# programmer-board.net
KiCad netlist of a schematic drawn in EAGLE
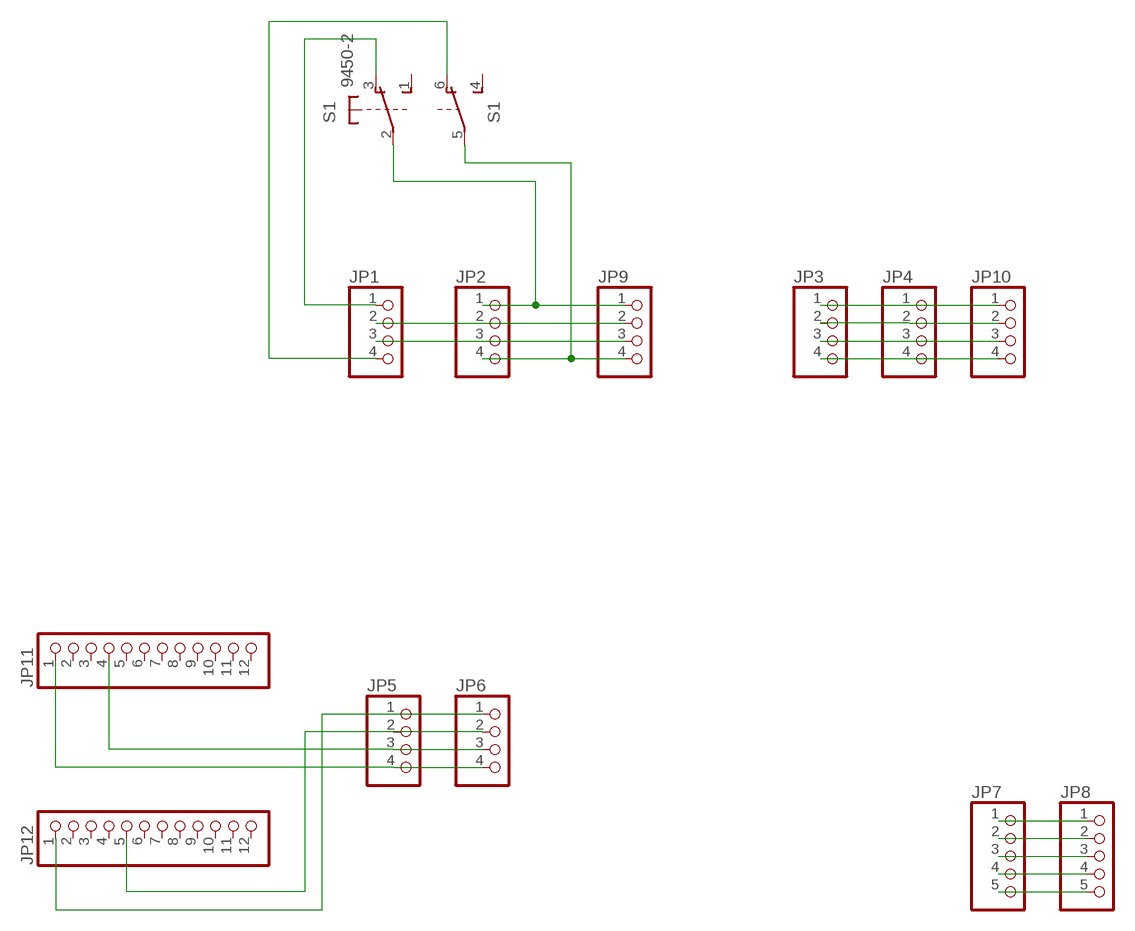
[diagram p0: schematic, sheet 1]

(export (version "E")
  (design (tool "Eeschema 10.0.6"))
  (components
    (comp (ref "JP1")
      (value "PINHD-1X4")
      (footprint "eagle-import:1X04")
      (libsource (lib "eagle-import") (part "PINHD-1X4"))
    )
    (comp (ref "JP2")
      (value "PINHD-1X4")
      (footprint "eagle-import:1X04")
      (libsource (lib "eagle-import") (part "PINHD-1X4"))
    )
    (comp (ref "JP3")
      (value "PINHD-1X4")
      (footprint "eagle-import:1X04")
      (libsource (lib "eagle-import") (part "PINHD-1X4"))
    )
    (comp (ref "JP4")
      (value "PINHD-1X4")
      (footprint "eagle-import:1X04")
      (libsource (lib "eagle-import") (part "PINHD-1X4"))
    )
    (comp (ref "JP5")
      (value "PINHD-1X4")
      (footprint "eagle-import:1X04")
      (libsource (lib "eagle-import") (part "PINHD-1X4"))
    )
    (comp (ref "JP6")
      (value "PINHD-1X4")
      (footprint "eagle-import:1X04")
      (libsource (lib "eagle-import") (part "PINHD-1X4"))
    )
    (comp (ref "JP7")
      (value "PINHD-1X5")
      (footprint "eagle-import:1X05")
      (libsource (lib "eagle-import") (part "PINHD-1X5"))
    )
    (comp (ref "JP8")
      (value "PINHD-1X5")
      (footprint "eagle-import:1X05")
      (libsource (lib "eagle-import") (part "PINHD-1X5"))
    )
    (comp (ref "JP9")
      (value "PINHD-1X4")
      (footprint "eagle-import:1X04")
      (libsource (lib "eagle-import") (part "PINHD-1X4"))
    )
    (comp (ref "JP10")
      (value "PINHD-1X4")
      (footprint "eagle-import:1X04")
      (libsource (lib "eagle-import") (part "PINHD-1X4"))
    )
    (comp (ref "JP11")
      (value "PINHD-1X12")
      (footprint "eagle-import:1X12")
      (libsource (lib "eagle-import") (part "PINHD-1X12"))
    )
    (comp (ref "JP12")
      (value "PINHD-1X12")
      (footprint "eagle-import:1X12")
      (libsource (lib "eagle-import") (part "PINHD-1X12"))
    )
    (comp (ref "S1")
      (value "9450-2")
      (footprint "eagle-import:9450-2")
      (libsource (lib "eagle-import") (part "9450-2"))
    )
  )
  (nets
    (net (code "1") (name "Net-(JP1-Pad2)") (class "Default")
      (node (ref "JP1") (pin "2") (pinfunction "2_2") (pintype "passive"))
      (node (ref "JP2") (pin "2") (pinfunction "2_2") (pintype "passive"))
      (node (ref "JP9") (pin "2") (pinfunction "2_2") (pintype "passive"))
    )
    (net (code "2") (name "Net-(JP1-Pad3)") (class "Default")
      (node (ref "JP1") (pin "3") (pinfunction "3_3") (pintype "passive"))
      (node (ref "JP2") (pin "3") (pinfunction "3_3") (pintype "passive"))
      (node (ref "JP9") (pin "3") (pinfunction "3_3") (pintype "passive"))
    )
    (net (code "3") (name "Net-(JP7-Pad1)") (class "Default")
      (node (ref "JP7") (pin "1") (pinfunction "1_1") (pintype "passive"))
      (node (ref "JP8") (pin "1") (pinfunction "1_1") (pintype "passive"))
    )
    (net (code "4") (name "Net-(JP7-Pad2)") (class "Default")
      (node (ref "JP7") (pin "2") (pinfunction "2_2") (pintype "passive"))
      (node (ref "JP8") (pin "2") (pinfunction "2_2") (pintype "passive"))
    )
    (net (code "5") (name "Net-(JP7-Pad3)") (class "Default")
      (node (ref "JP7") (pin "3") (pinfunction "3_3") (pintype "passive"))
      (node (ref "JP8") (pin "3") (pinfunction "3_3") (pintype "passive"))
    )
    (net (code "6") (name "Net-(JP7-Pad4)") (class "Default")
      (node (ref "JP7") (pin "4") (pinfunction "4_4") (pintype "passive"))
      (node (ref "JP8") (pin "4") (pinfunction "4_4") (pintype "passive"))
    )
    (net (code "7") (name "Net-(JP7-Pad5)") (class "Default")
      (node (ref "JP7") (pin "5") (pinfunction "5_5") (pintype "passive"))
      (node (ref "JP8") (pin "5") (pinfunction "5_5") (pintype "passive"))
    )
    (net (code "8") (name "Net-(JP10-Pad1)") (class "Default")
      (node (ref "JP10") (pin "1") (pinfunction "1_1") (pintype "passive"))
      (node (ref "JP3") (pin "1") (pinfunction "1_1") (pintype "passive"))
      (node (ref "JP4") (pin "1") (pinfunction "1_1") (pintype "passive"))
    )
    (net (code "9") (name "Net-(JP10-Pad2)") (class "Default")
      (node (ref "JP10") (pin "2") (pinfunction "2_2") (pintype "passive"))
      (node (ref "JP3") (pin "2") (pinfunction "2_2") (pintype "passive"))
      (node (ref "JP4") (pin "2") (pinfunction "2_2") (pintype "passive"))
    )
    (net (code "10") (name "Net-(JP10-Pad3)") (class "Default")
      (node (ref "JP10") (pin "3") (pinfunction "3_3") (pintype "passive"))
      (node (ref "JP3") (pin "3") (pinfunction "3_3") (pintype "passive"))
      (node (ref "JP4") (pin "3") (pinfunction "3_3") (pintype "passive"))
    )
    (net (code "11") (name "Net-(JP10-Pad4)") (class "Default")
      (node (ref "JP10") (pin "4") (pinfunction "4_4") (pintype "passive"))
      (node (ref "JP3") (pin "4") (pinfunction "4_4") (pintype "passive"))
      (node (ref "JP4") (pin "4") (pinfunction "4_4") (pintype "passive"))
    )
    (net (code "12") (name "Net-(JP11-Pad1)") (class "Default")
      (node (ref "JP11") (pin "1") (pinfunction "1_1") (pintype "passive"))
      (node (ref "JP5") (pin "4") (pinfunction "4_4") (pintype "passive"))
      (node (ref "JP6") (pin "4") (pinfunction "4_4") (pintype "passive"))
    )
    (net (code "13") (name "Net-(JP11-Pad4)") (class "Default")
      (node (ref "JP11") (pin "4") (pinfunction "4_4") (pintype "passive"))
      (node (ref "JP5") (pin "3") (pinfunction "3_3") (pintype "passive"))
      (node (ref "JP6") (pin "3") (pinfunction "3_3") (pintype "passive"))
    )
    (net (code "14") (name "Net-(JP12-Pad1)") (class "Default")
      (node (ref "JP12") (pin "1") (pinfunction "1_1") (pintype "passive"))
      (node (ref "JP5") (pin "1") (pinfunction "1_1") (pintype "passive"))
      (node (ref "JP6") (pin "1") (pinfunction "1_1") (pintype "passive"))
    )
    (net (code "15") (name "Net-(JP12-Pad5)") (class "Default")
      (node (ref "JP12") (pin "5") (pinfunction "5_5") (pintype "passive"))
      (node (ref "JP5") (pin "2") (pinfunction "2_2") (pintype "passive"))
      (node (ref "JP6") (pin "2") (pinfunction "2_2") (pintype "passive"))
    )
    (net (code "16") (name "Net-(S1A-O)") (class "Default")
      (node (ref "JP1") (pin "1") (pinfunction "1_1") (pintype "passive"))
      (node (ref "S1") (pin "3") (pinfunction "O_3") (pintype "passive"))
    )
    (net (code "17") (name "Net-(S1A-P)") (class "Default")
      (node (ref "JP2") (pin "1") (pinfunction "1_1") (pintype "passive"))
      (node (ref "JP9") (pin "1") (pinfunction "1_1") (pintype "passive"))
      (node (ref "S1") (pin "2") (pinfunction "P_2") (pintype "passive"))
    )
    (net (code "18") (name "Net-(S1B-O)") (class "Default")
      (node (ref "JP1") (pin "4") (pinfunction "4_4") (pintype "passive"))
      (node (ref "S1") (pin "6") (pinfunction "O_6") (pintype "passive"))
    )
    (net (code "19") (name "Net-(S1B-P)") (class "Default")
      (node (ref "JP2") (pin "4") (pinfunction "4_4") (pintype "passive"))
      (node (ref "JP9") (pin "4") (pinfunction "4_4") (pintype "passive"))
      (node (ref "S1") (pin "5") (pinfunction "P_5") (pintype "passive"))
    )
    (net (code "20") (name "unconnected-(JP11-Pad2)") (class "Default")
      (node (ref "JP11") (pin "2") (pinfunction "2_2") (pintype "passive"))
    )
    (net (code "21") (name "unconnected-(JP11-Pad3)") (class "Default")
      (node (ref "JP11") (pin "3") (pinfunction "3_3") (pintype "passive"))
    )
    (net (code "22") (name "unconnected-(JP11-Pad5)") (class "Default")
      (node (ref "JP11") (pin "5") (pinfunction "5_5") (pintype "passive"))
    )
    (net (code "23") (name "unconnected-(JP11-Pad6)") (class "Default")
      (node (ref "JP11") (pin "6") (pinfunction "6_6") (pintype "passive"))
    )
    (net (code "24") (name "unconnected-(JP11-Pad7)") (class "Default")
      (node (ref "JP11") (pin "7") (pinfunction "7_7") (pintype "passive"))
    )
    (net (code "25") (name "unconnected-(JP11-Pad8)") (class "Default")
      (node (ref "JP11") (pin "8") (pinfunction "8_8") (pintype "passive"))
    )
    (net (code "26") (name "unconnected-(JP11-Pad9)") (class "Default")
      (node (ref "JP11") (pin "9") (pinfunction "9_9") (pintype "passive"))
    )
    (net (code "27") (name "unconnected-(JP11-Pad10)") (class "Default")
      (node (ref "JP11") (pin "10") (pinfunction "10_10") (pintype "passive"))
    )
    (net (code "28") (name "unconnected-(JP11-Pad11)") (class "Default")
      (node (ref "JP11") (pin "11") (pinfunction "11_11") (pintype "passive"))
    )
    (net (code "29") (name "unconnected-(JP11-Pad12)") (class "Default")
      (node (ref "JP11") (pin "12") (pinfunction "12_12") (pintype "passive"))
    )
    (net (code "30") (name "unconnected-(JP12-Pad2)") (class "Default")
      (node (ref "JP12") (pin "2") (pinfunction "2_2") (pintype "passive"))
    )
    (net (code "31") (name "unconnected-(JP12-Pad3)") (class "Default")
      (node (ref "JP12") (pin "3") (pinfunction "3_3") (pintype "passive"))
    )
    (net (code "32") (name "unconnected-(JP12-Pad4)") (class "Default")
      (node (ref "JP12") (pin "4") (pinfunction "4_4") (pintype "passive"))
    )
    (net (code "33") (name "unconnected-(JP12-Pad6)") (class "Default")
      (node (ref "JP12") (pin "6") (pinfunction "6_6") (pintype "passive"))
    )
    (net (code "34") (name "unconnected-(JP12-Pad7)") (class "Default")
      (node (ref "JP12") (pin "7") (pinfunction "7_7") (pintype "passive"))
    )
    (net (code "35") (name "unconnected-(JP12-Pad8)") (class "Default")
      (node (ref "JP12") (pin "8") (pinfunction "8_8") (pintype "passive"))
    )
    (net (code "36") (name "unconnected-(JP12-Pad9)") (class "Default")
      (node (ref "JP12") (pin "9") (pinfunction "9_9") (pintype "passive"))
    )
    (net (code "37") (name "unconnected-(JP12-Pad10)") (class "Default")
      (node (ref "JP12") (pin "10") (pinfunction "10_10") (pintype "passive"))
    )
    (net (code "38") (name "unconnected-(JP12-Pad11)") (class "Default")
      (node (ref "JP12") (pin "11") (pinfunction "11_11") (pintype "passive"))
    )
    (net (code "39") (name "unconnected-(JP12-Pad12)") (class "Default")
      (node (ref "JP12") (pin "12") (pinfunction "12_12") (pintype "passive"))
    )
    (net (code "40") (name "unconnected-(S1A-S-Pad1)") (class "Default")
      (node (ref "S1") (pin "1") (pinfunction "S_1") (pintype "passive"))
    )
    (net (code "41") (name "unconnected-(S1B-S-Pad4)") (class "Default")
      (node (ref "S1") (pin "4") (pinfunction "S_4") (pintype "passive"))
    )
  )
)
